# photoDetector.net
KiCad netlist of a schematic drawn in Altium Designer
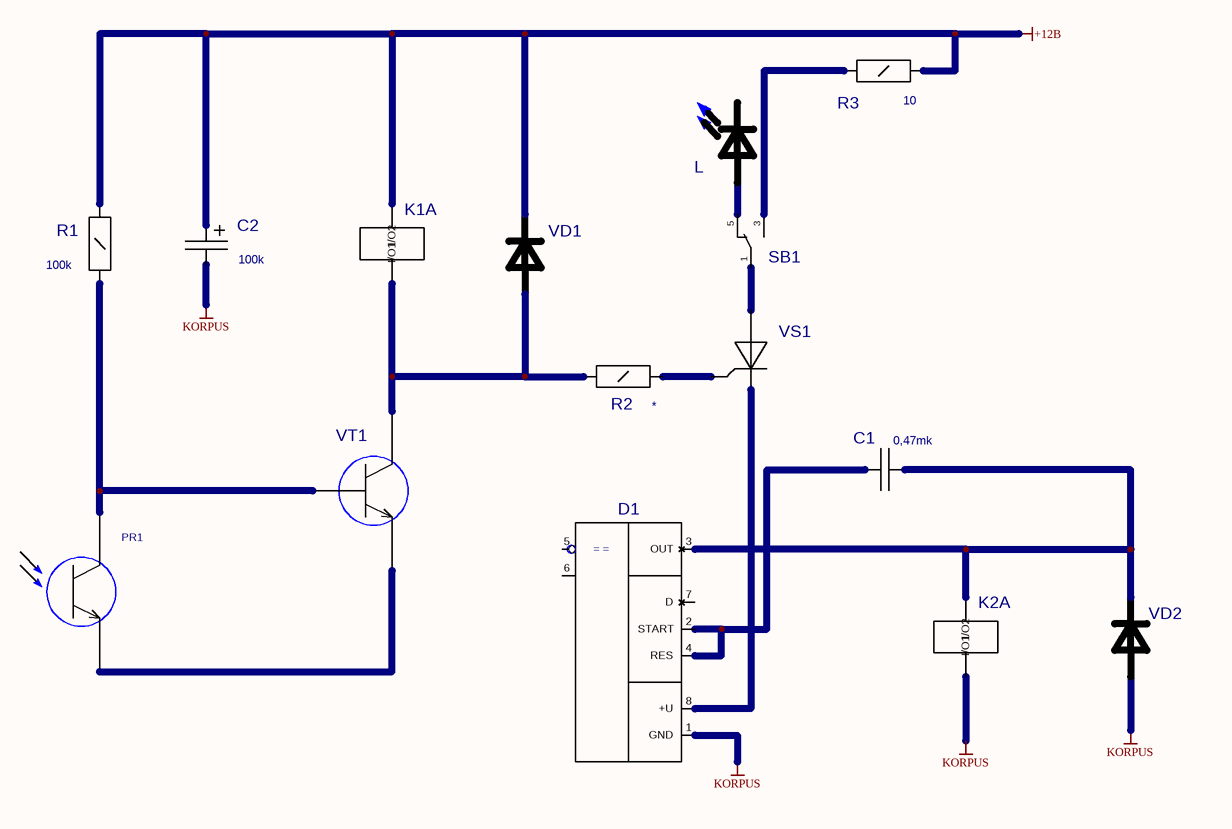
[diagram p0: photoDetector.SchDoc]

(export (version "E")
  (design (tool "Eeschema 10.0.6"))
  (components
    (comp (ref "C1")
      (value "0,47mk")
      (footprint "CC2220")
      (description "CC2220")
      (libsource (lib "*") (part "CC2220"))
    )
    (comp (ref "C2")
      (value "100k")
      (footprint "CE6032_C")
      (description "CE6032-C")
      (libsource (lib "*") (part "CE6032-C"))
    )
    (comp (ref "D1") (value "KR1006VI1") (footprint "DIP8") (libsource (lib "*") (part "KR1006VI1")))
    (comp (ref "K1") (value "РЭС-64") (footprint "RES64") (libsource (lib "*") (part "РЭС-64")))
    (comp (ref "K2") (value "РЭС-64") (footprint "RES64") (libsource (lib "*") (part "РЭС-64")))
    (comp (ref "L") (value "АЛ307КМ") (footprint "LED-5MM") (libsource (lib "*") (part "АЛ307КМ")))
    (comp (ref "PR1") (value "L-53P3C") (footprint "L-53P3C") (libsource (lib "*") (part "L-53P3C")))
    (comp (ref "R1")
      (value "100k")
      (footprint "C2-33H-0.25W")
      (description "C2-33H-0.25W_OLD_UGO")
      (fields (field (name "AUTOR") "pcbdesigner.ru"))
      (libsource (lib "") (part "C2-33H-0.25W_OLD_UGO_1"))
    )
    (comp (ref "R2")
      (value "C2-33H-0.25W_OLD_UGO")
      (footprint "C2-33H-0.25W")
      (fields (field (name "ALTIUM_VALUE") "*") (field (name "AUTOR") "pcbdesigner.ru"))
      (libsource (lib "*") (part "C2-33H-0.25W_OLD_UGO"))
    )
    (comp (ref "R3")
      (value "10")
      (footprint "C2-33H-0.25W")
      (description "C2-33H-0.25W_OLD_UGO")
      (fields (field (name "AUTOR") "pcbdesigner.ru"))
      (libsource (lib "") (part "C2-33H-0.25W_OLD_UGO_1"))
    )
    (comp (ref "SB1")
      (value "CB-6600")
      (footprint "CB-6600")
      (fields (field (name "AUTHOR") "pcbdesigner.ru"))
      (libsource (lib "*") (part "CB-6600"))
    )
    (comp (ref "VD1") (value "КД521Б") (footprint "КД521(522)") (libsource (lib "*") (part "КД521Б")))
    (comp (ref "VD2") (value "КД521Б") (footprint "КД521(522)") (libsource (lib "*") (part "КД521Б")))
    (comp (ref "VS1") (value "KU101") (footprint "KU101") (libsource (lib "*") (part "KU101")))
    (comp (ref "VT1") (value "КТ315Б") (footprint "KT13") (libsource (lib "*") (part "КТ315Б")))
  )
  (nets
    (net (code "1") (name "+12B") (class "Default")
      (node (ref "C2") (pin "1") (pinfunction "1_1") (pintype "passive"))
      (node (ref "K1") (pin "2") (pinfunction "I/O2_2") (pintype "passive"))
      (node (ref "R1") (pin "2") (pinfunction "2_2") (pintype "passive"))
      (node (ref "R3") (pin "1") (pinfunction "1_1") (pintype "passive"))
      (node (ref "VD1") (pin "2") (pinfunction "K_2") (pintype "passive"))
    )
    (net (code "2") (name "KORPUS") (class "Default")
      (node (ref "C2") (pin "2") (pinfunction "2_2") (pintype "passive"))
      (node (ref "D1") (pin "1") (pinfunction "GND_1") (pintype "passive"))
      (node (ref "K2") (pin "1") (pinfunction "I/O1_1") (pintype "passive"))
      (node (ref "VD2") (pin "1") (pinfunction "A_1") (pintype "passive"))
    )
    (net (code "3") (name "Net-(D1-+U)") (class "Default")
      (node (ref "D1") (pin "8") (pinfunction "+U_8") (pintype "passive"))
      (node (ref "VS1") (pin "2") (pinfunction "I/OB_2") (pintype "passive"))
    )
    (net (code "4") (name "Net-(D1-OUT)") (class "Default")
      (node (ref "C1") (pin "2") (pinfunction "2_2") (pintype "passive"))
      (node (ref "D1") (pin "3") (pinfunction "OUT_3") (pintype "passive"))
      (node (ref "K2") (pin "2") (pinfunction "I/O2_2") (pintype "passive"))
      (node (ref "VD2") (pin "2") (pinfunction "K_2") (pintype "passive"))
    )
    (net (code "5") (name "Net-(D1-RES)") (class "Default")
      (node (ref "C1") (pin "1") (pinfunction "1_1") (pintype "passive"))
      (node (ref "D1") (pin "2") (pinfunction "START_2") (pintype "passive"))
      (node (ref "D1") (pin "4") (pinfunction "RES_4") (pintype "passive"))
    )
    (net (code "6") (name "Net-(K1-I{slash}O1)") (class "Default")
      (node (ref "K1") (pin "1") (pinfunction "I/O1_1") (pintype "passive"))
      (node (ref "R2") (pin "2") (pinfunction "2_2") (pintype "passive"))
      (node (ref "VD1") (pin "1") (pinfunction "A_1") (pintype "passive"))
      (node (ref "VT1") (pin "3") (pinfunction "K_3") (pintype "passive"))
    )
    (net (code "7") (name "Net-(L-A)") (class "Default")
      (node (ref "L") (pin "1") (pinfunction "A_1") (pintype "passive"))
      (node (ref "SB1") (pin "5") (pinfunction "3_5") (pintype "passive"))
    )
    (net (code "8") (name "Net-(PR1-1)") (class "Default")
      (node (ref "PR1") (pin "K") (pinfunction "1_K") (pintype "passive"))
      (node (ref "R1") (pin "1") (pinfunction "1_1") (pintype "passive"))
      (node (ref "VT1") (pin "2") (pinfunction "B_2") (pintype "passive"))
    )
    (net (code "9") (name "Net-(PR1-2)") (class "Default")
      (node (ref "PR1") (pin "E") (pinfunction "2_E") (pintype "passive"))
      (node (ref "VT1") (pin "1") (pinfunction "E_1") (pintype "passive"))
    )
    (net (code "10") (name "Net-(SB1-2)") (class "Default")
      (node (ref "R3") (pin "2") (pinfunction "2_2") (pintype "passive"))
      (node (ref "SB1") (pin "3") (pinfunction "2_3") (pintype "passive"))
    )
    (net (code "11") (name "Net-(VS1-IN)") (class "Default")
      (node (ref "R2") (pin "1") (pinfunction "1_1") (pintype "passive"))
      (node (ref "VS1") (pin "3") (pinfunction "IN_3") (pintype "passive"))
    )
    (net (code "12") (name "Net-(VS1-I{slash}OA)") (class "Default")
      (node (ref "SB1") (pin "1") (pinfunction "1_1") (pintype "passive"))
      (node (ref "VS1") (pin "1") (pinfunction "I/OA_1") (pintype "passive"))
    )
    (net (code "13") (name "unconnected-(D1-D-Pad7)") (class "Default")
      (node (ref "D1") (pin "7") (pinfunction "D_7") (pintype "passive"))
    )
    (net (code "14") (name "unconnected-(D1-IN1-Pad5)") (class "Default")
      (node (ref "D1") (pin "5") (pinfunction "IN1_5") (pintype "passive"))
    )
    (net (code "15") (name "unconnected-(D1-IN2-Pad6)") (class "Default")
      (node (ref "D1") (pin "6") (pinfunction "IN2_6") (pintype "passive"))
    )
    (net (code "16") (name "unconnected-(K1-Pad5)") (class "Default")
      (node (ref "K1") (pin "5") (pintype "passive"))
    )
    (net (code "17") (name "unconnected-(K2-Pad5)") (class "Default")
      (node (ref "K2") (pin "5") (pintype "passive"))
    )
    (net (code "18") (name "unconnected-(L-K-Pad2)") (class "Default")
      (node (ref "L") (pin "2") (pinfunction "K_2") (pintype "passive"))
    )
    (net (code "19") (name "unconnected-(SB1-Pad2)") (class "Default")
      (node (ref "SB1") (pin "2") (pintype "passive"))
    )
    (net (code "20") (name "unconnected-(SB1-Pad4)") (class "Default")
      (node (ref "SB1") (pin "4") (pintype "passive"))
    )
  )
)
